# Sheet2.net
KiCad netlist of a schematic drawn in Altium Designer
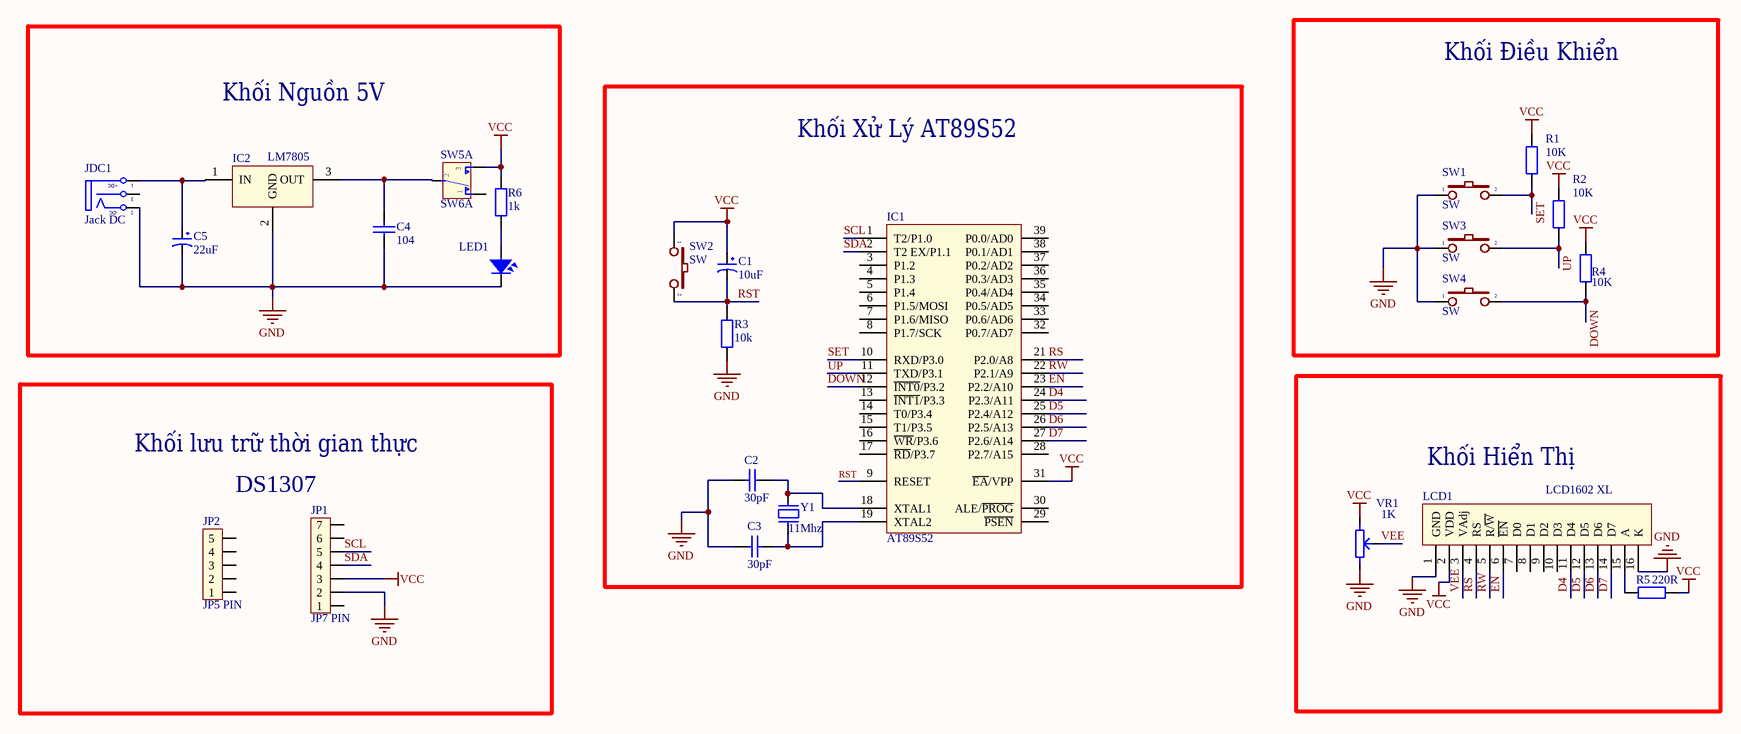
[diagram p0: Sheet2 (1).SchDoc]

(export (version "E")
  (design (tool "Eeschema 10.0.6"))
  (components
    (comp (ref "C1")
      (value "10uF")
      (footprint "tu hoa 4mm")
      (description "Cắm")
      (libsource (lib "Capacitor") (part "Tu Hoa 10uF 25V 4x7"))
    )
    (comp (ref "C2")
      (value "30pF")
      (footprint "tu gom")
      (description "Cắm")
      (libsource (lib "Capacitor") (part "Tu gom 30pF 50V"))
    )
    (comp (ref "C3")
      (value "30pF")
      (footprint "tu gom")
      (description "Cắm")
      (libsource (lib "Capacitor") (part "Tu gom 30pF 50V"))
    )
    (comp (ref "C4")
      (value "104")
      (footprint "tu gom")
      (description "Cắm")
      (libsource (lib "Capacitor") (part "Tu gom 104 50V"))
    )
    (comp (ref "C5")
      (value "22uF")
      (footprint "tu hoa 5mm")
      (description "Cắm")
      (libsource (lib "Capacitor") (part "Tu Hoa 22uF 50V 5x10"))
    )
    (comp (ref "IC1")
      (value "AT89S52")
      (footprint "DIP40/W0.6")
      (description "AT89S52, 8k Byte Flash Memory , 40 Pin")
      (libsource (lib "syhaunguyen") (part "AT89S52"))
    )
    (comp (ref "IC2")
      (value "LM7805")
      (footprint "QTO-220")
      (description "On ap +, from + 5 to + 24VDC")
      (libsource (lib "syhaunguyen") (part "LM78xx"))
    )
    (comp (ref "JDC1")
      (value "Jack DC")
      (footprint "DC-IN")
      (description "Jac DC input")
      (libsource (lib "syhaunguyen") (part "DCIN"))
    )
    (comp (ref "JP1") (value "JP7 PIN") (footprint "JP7_1") (libsource (lib "Cty1") (part "JP7")))
    (comp (ref "JP2") (value "JP5 PIN") (footprint "JP5_1") (libsource (lib "Cty1") (part "JP5")))
    (comp (ref "LCD1")
      (value "LCD1602 XL")
      (footprint "LCD1602 with Jump")
      (description "LCD 1602 Xanh Lá")
      (libsource (lib "Module") (part "LCD1602 XL"))
    )
    (comp (ref "LED1")
      (value "LED")
      (footprint "LED-5-RED")
      (description "LED Single colour Green and Red")
      (libsource (lib "syhaunguyen") (part "LED"))
    )
    (comp (ref "R1")
      (value "10K")
      (footprint "tro vach 1/4w")
      (description "Cắm")
      (libsource (lib "Resistor") (part "Tro Vach 1/4W 5% 220R"))
    )
    (comp (ref "R2")
      (value "10K")
      (footprint "tro vach 1/4w")
      (description "Cắm")
      (libsource (lib "Resistor") (part "Tro Vach 1/4W 5% 220R"))
    )
    (comp (ref "R3")
      (value "10k")
      (footprint "tro vach 1/4w")
      (description "Căm")
      (libsource (lib "Resistor") (part "Tro Vach 1/4W 5% 10k"))
    )
    (comp (ref "R4")
      (value "10K")
      (footprint "tro vach 1/4w")
      (description "Cắm")
      (libsource (lib "Resistor") (part "Tro Vach 1/4W 5% 220R"))
    )
    (comp (ref "R5")
      (value "220R")
      (footprint "tro vach 1/4w")
      (description "Cắm")
      (libsource (lib "Resistor") (part "Tro Vach 1/4W 5% 220R"))
    )
    (comp (ref "R6")
      (value "1k")
      (footprint "R1/4W")
      (description "Resistor 1/4W")
      (libsource (lib "syhaunguyen") (part "R1/4W"))
    )
    (comp (ref "SW1")
      (value "SW")
      (footprint "SW2")
      (description "Switch button 2 pin")
      (libsource (lib "syhaunguyen") (part "SW2"))
    )
    (comp (ref "SW2")
      (value "SW")
      (footprint "SW2")
      (description "Switch button 2 pin")
      (libsource (lib "syhaunguyen") (part "SW2"))
    )
    (comp (ref "SW3")
      (value "SW")
      (footprint "SW2")
      (description "Switch button 2 pin")
      (libsource (lib "syhaunguyen") (part "SW2"))
    )
    (comp (ref "SW4")
      (value "SW")
      (footprint "SW2")
      (description "Switch button 2 pin")
      (libsource (lib "syhaunguyen") (part "SW2"))
    )
    (comp (ref "SW5")
      (value "SW6A")
      (footprint "SW6")
      (description "SW-DTDP - 6 Pin")
      (libsource (lib "syhaunguyen") (part "SW6A"))
    )
    (comp (ref "VR1")
      (value "1K")
      (footprint "Bien Tro Tam Giac Dung")
      (description "Cắm")
      (libsource (lib "Resistor") (part "Bien tro tam giac 1K Dung"))
    )
    (comp (ref "Y1")
      (value "11Mhz")
      (footprint "Thach Anh 2 chan cam")
      (description "Crystal For all Crystal 2pin.")
      (libsource (lib "Component") (part "Thach Anh 2 chan Cam"))
    )
  )
  (nets
    (net (code "1") (name "/D4") (class "Default")
      (node (ref "IC1") (pin "24") (pinfunction "P2.3/A11_24") (pintype "passive"))
      (node (ref "LCD1") (pin "11") (pinfunction "D4_11") (pintype "passive"))
    )
    (net (code "2") (name "/D5") (class "Default")
      (node (ref "IC1") (pin "25") (pinfunction "P2.4/A12_25") (pintype "passive"))
      (node (ref "LCD1") (pin "12") (pinfunction "D5_12") (pintype "passive"))
    )
    (net (code "3") (name "/D6") (class "Default")
      (node (ref "IC1") (pin "26") (pinfunction "P2.5/A13_26") (pintype "passive"))
      (node (ref "LCD1") (pin "13") (pinfunction "D6_13") (pintype "passive"))
    )
    (net (code "4") (name "/D7") (class "Default")
      (node (ref "IC1") (pin "27") (pinfunction "P2.6/A14_27") (pintype "passive"))
      (node (ref "LCD1") (pin "14") (pinfunction "D7_14") (pintype "passive"))
    )
    (net (code "5") (name "/DOWN") (class "Default")
      (node (ref "IC1") (pin "12") (pinfunction "~{INT0}/P3.2_12") (pintype "passive"))
      (node (ref "R4") (pin "2") (pinfunction "2_2") (pintype "passive"))
      (node (ref "SW4") (pin "2") (pinfunction "2_2") (pintype "passive"))
    )
    (net (code "6") (name "/EN") (class "Default")
      (node (ref "IC1") (pin "23") (pinfunction "P2.2/A10_23") (pintype "passive"))
      (node (ref "LCD1") (pin "6") (pinfunction "~{EN}_6") (pintype "passive"))
    )
    (net (code "7") (name "/RS") (class "Default")
      (node (ref "IC1") (pin "21") (pinfunction "P2.0/A8_21") (pintype "passive"))
      (node (ref "LCD1") (pin "4") (pinfunction "RS_4") (pintype "passive"))
    )
    (net (code "8") (name "/RST") (class "Default")
      (node (ref "C1") (pin "2") (pinfunction "2_2") (pintype "passive"))
      (node (ref "IC1") (pin "9") (pinfunction "RESET_9") (pintype "passive"))
      (node (ref "R3") (pin "2") (pinfunction "2_2") (pintype "passive"))
      (node (ref "SW2") (pin "2") (pinfunction "2_2") (pintype "passive"))
    )
    (net (code "9") (name "/RW") (class "Default")
      (node (ref "IC1") (pin "22") (pinfunction "P2.1/A9_22") (pintype "passive"))
      (node (ref "LCD1") (pin "5") (pinfunction "R/~{W}_5") (pintype "passive"))
    )
    (net (code "10") (name "/SCL") (class "Default")
      (node (ref "IC1") (pin "1") (pinfunction "T2/P1.0_1") (pintype "passive"))
      (node (ref "JP1") (pin "5") (pinfunction "5_5") (pintype "passive"))
    )
    (net (code "11") (name "/SDA") (class "Default")
      (node (ref "IC1") (pin "2") (pinfunction "T2_EX/P1.1_2") (pintype "passive"))
      (node (ref "JP1") (pin "4") (pinfunction "4_4") (pintype "passive"))
    )
    (net (code "12") (name "/SET") (class "Default")
      (node (ref "IC1") (pin "10") (pinfunction "RXD/P3.0_10") (pintype "passive"))
      (node (ref "R1") (pin "2") (pinfunction "2_2") (pintype "passive"))
      (node (ref "SW1") (pin "2") (pinfunction "2_2") (pintype "passive"))
    )
    (net (code "13") (name "/UP") (class "Default")
      (node (ref "IC1") (pin "11") (pinfunction "TXD/P3.1_11") (pintype "passive"))
      (node (ref "R2") (pin "2") (pinfunction "2_2") (pintype "passive"))
      (node (ref "SW3") (pin "2") (pinfunction "2_2") (pintype "passive"))
    )
    (net (code "14") (name "/VEE") (class "Default")
      (node (ref "LCD1") (pin "3") (pinfunction "VAdj_3") (pintype "passive"))
      (node (ref "VR1") (pin "2") (pinfunction "2_2") (pintype "passive"))
    )
    (net (code "15") (name "GND") (class "Default")
      (node (ref "C2") (pin "2") (pinfunction "2_2") (pintype "passive"))
      (node (ref "C3") (pin "2") (pinfunction "2_2") (pintype "passive"))
      (node (ref "C4") (pin "2") (pinfunction "2_2") (pintype "passive"))
      (node (ref "C5") (pin "2") (pinfunction "2_2") (pintype "passive"))
      (node (ref "IC1") (pin "20") (pinfunction "GND_20") (pintype "power_in"))
      (node (ref "IC2") (pin "2") (pinfunction "GND_2") (pintype "passive"))
      (node (ref "JDC1") (pin "2") (pinfunction "TN_2") (pintype "passive"))
      (node (ref "JP1") (pin "2") (pinfunction "2_2") (pintype "passive"))
      (node (ref "LCD1") (pin "1") (pinfunction "GND_1") (pintype "passive"))
      (node (ref "LCD1") (pin "16") (pinfunction "K_16") (pintype "passive"))
      (node (ref "LED1") (pin "2") (pinfunction "2_2") (pintype "passive"))
      (node (ref "R3") (pin "1") (pinfunction "1_1") (pintype "passive"))
      (node (ref "SW1") (pin "1") (pinfunction "1_1") (pintype "passive"))
      (node (ref "SW3") (pin "1") (pinfunction "1_1") (pintype "passive"))
      (node (ref "SW4") (pin "1") (pinfunction "1_1") (pintype "passive"))
      (node (ref "VR1") (pin "3") (pinfunction "3_3") (pintype "passive"))
    )
    (net (code "16") (name "Net-(IC1-XTAL1)") (class "Default")
      (node (ref "C2") (pin "1") (pinfunction "1_1") (pintype "passive"))
      (node (ref "IC1") (pin "18") (pinfunction "XTAL1_18") (pintype "passive"))
      (node (ref "Y1") (pin "2") (pinfunction "2_2") (pintype "passive"))
    )
    (net (code "17") (name "Net-(IC1-XTAL2)") (class "Default")
      (node (ref "C3") (pin "1") (pinfunction "1_1") (pintype "passive"))
      (node (ref "IC1") (pin "19") (pinfunction "XTAL2_19") (pintype "passive"))
      (node (ref "Y1") (pin "1") (pinfunction "1_1") (pintype "passive"))
    )
    (net (code "18") (name "Net-(IC2-IN)") (class "Default")
      (node (ref "C5") (pin "1") (pinfunction "1_1") (pintype "passive"))
      (node (ref "IC2") (pin "1") (pinfunction "IN_1") (pintype "passive"))
      (node (ref "JDC1") (pin "1") (pinfunction "T_1") (pintype "passive"))
    )
    (net (code "19") (name "Net-(IC2-OUT)") (class "Default")
      (node (ref "C4") (pin "1") (pinfunction "1_1") (pintype "passive"))
      (node (ref "IC2") (pin "3") (pinfunction "OUT_3") (pintype "passive"))
      (node (ref "SW5") (pin "2") (pinfunction "2_2") (pintype "passive"))
    )
    (net (code "20") (name "Net-(LCD1-A)") (class "Default")
      (node (ref "LCD1") (pin "15") (pinfunction "A_15") (pintype "passive"))
      (node (ref "R5") (pin "2") (pinfunction "2_2") (pintype "passive"))
    )
    (net (code "21") (name "Net-(LED1-Pad1)") (class "Default")
      (node (ref "LED1") (pin "1") (pinfunction "1_1") (pintype "passive"))
      (node (ref "R6") (pin "1") (pinfunction "1_1") (pintype "passive"))
    )
    (net (code "22") (name "VCC") (class "Default")
      (node (ref "C1") (pin "1") (pinfunction "1_1") (pintype "passive"))
      (node (ref "IC1") (pin "31") (pinfunction "~{EA}/VPP_31") (pintype "passive"))
      (node (ref "IC1") (pin "40") (pinfunction "VCC_40") (pintype "power_in"))
      (node (ref "JP1") (pin "3") (pinfunction "3_3") (pintype "passive"))
      (node (ref "LCD1") (pin "2") (pinfunction "VDD_2") (pintype "passive"))
      (node (ref "R1") (pin "1") (pinfunction "1_1") (pintype "passive"))
      (node (ref "R2") (pin "1") (pinfunction "1_1") (pintype "passive"))
      (node (ref "R4") (pin "1") (pinfunction "1_1") (pintype "passive"))
      (node (ref "R5") (pin "1") (pinfunction "1_1") (pintype "passive"))
      (node (ref "R6") (pin "2") (pinfunction "2_2") (pintype "passive"))
      (node (ref "SW2") (pin "1") (pinfunction "1_1") (pintype "passive"))
      (node (ref "SW5") (pin "3") (pinfunction "3_3") (pintype "passive"))
      (node (ref "VR1") (pin "1") (pinfunction "1_1") (pintype "passive"))
    )
    (net (code "23") (name "unconnected-(IC1-ALE{slash}~{PROG}-Pad30)") (class "Default")
      (node (ref "IC1") (pin "30") (pinfunction "ALE/~{PROG}_30") (pintype "passive"))
    )
    (net (code "24") (name "unconnected-(IC1-P0.0{slash}AD0-Pad39)") (class "Default")
      (node (ref "IC1") (pin "39") (pinfunction "P0.0/AD0_39") (pintype "passive"))
    )
    (net (code "25") (name "unconnected-(IC1-P0.1{slash}AD1-Pad38)") (class "Default")
      (node (ref "IC1") (pin "38") (pinfunction "P0.1/AD1_38") (pintype "passive"))
    )
    (net (code "26") (name "unconnected-(IC1-P0.2{slash}AD2-Pad37)") (class "Default")
      (node (ref "IC1") (pin "37") (pinfunction "P0.2/AD2_37") (pintype "passive"))
    )
    (net (code "27") (name "unconnected-(IC1-P0.3{slash}AD3-Pad36)") (class "Default")
      (node (ref "IC1") (pin "36") (pinfunction "P0.3/AD3_36") (pintype "passive"))
    )
    (net (code "28") (name "unconnected-(IC1-P0.4{slash}AD4-Pad35)") (class "Default")
      (node (ref "IC1") (pin "35") (pinfunction "P0.4/AD4_35") (pintype "passive"))
    )
    (net (code "29") (name "unconnected-(IC1-P0.5{slash}AD5-Pad34)") (class "Default")
      (node (ref "IC1") (pin "34") (pinfunction "P0.5/AD5_34") (pintype "passive"))
    )
    (net (code "30") (name "unconnected-(IC1-P0.6{slash}AD6-Pad33)") (class "Default")
      (node (ref "IC1") (pin "33") (pinfunction "P0.6/AD6_33") (pintype "passive"))
    )
    (net (code "31") (name "unconnected-(IC1-P0.7{slash}AD7-Pad32)") (class "Default")
      (node (ref "IC1") (pin "32") (pinfunction "P0.7/AD7_32") (pintype "passive"))
    )
    (net (code "32") (name "unconnected-(IC1-P1.2-Pad3)") (class "Default")
      (node (ref "IC1") (pin "3") (pinfunction "P1.2_3") (pintype "passive"))
    )
    (net (code "33") (name "unconnected-(IC1-P1.3-Pad4)") (class "Default")
      (node (ref "IC1") (pin "4") (pinfunction "P1.3_4") (pintype "passive"))
    )
    (net (code "34") (name "unconnected-(IC1-P1.4-Pad5)") (class "Default")
      (node (ref "IC1") (pin "5") (pinfunction "P1.4_5") (pintype "passive"))
    )
    (net (code "35") (name "unconnected-(IC1-P1.5{slash}MOSI-Pad6)") (class "Default")
      (node (ref "IC1") (pin "6") (pinfunction "P1.5/MOSI_6") (pintype "passive"))
    )
    (net (code "36") (name "unconnected-(IC1-P1.6{slash}MISO-Pad7)") (class "Default")
      (node (ref "IC1") (pin "7") (pinfunction "P1.6/MISO_7") (pintype "passive"))
    )
    (net (code "37") (name "unconnected-(IC1-P1.7{slash}SCK-Pad8)") (class "Default")
      (node (ref "IC1") (pin "8") (pinfunction "P1.7/SCK_8") (pintype "passive"))
    )
    (net (code "38") (name "unconnected-(IC1-P2.7{slash}A15-Pad28)") (class "Default")
      (node (ref "IC1") (pin "28") (pinfunction "P2.7/A15_28") (pintype "passive"))
    )
    (net (code "39") (name "unconnected-(IC1-T0{slash}P3.4-Pad14)") (class "Default")
      (node (ref "IC1") (pin "14") (pinfunction "T0/P3.4_14") (pintype "passive"))
    )
    (net (code "40") (name "unconnected-(IC1-T1{slash}P3.5-Pad15)") (class "Default")
      (node (ref "IC1") (pin "15") (pinfunction "T1/P3.5_15") (pintype "passive"))
    )
    (net (code "41") (name "unconnected-(IC1-~{INT1}{slash}P3.3-Pad13)") (class "Default")
      (node (ref "IC1") (pin "13") (pinfunction "~{INT1}/P3.3_13") (pintype "passive"))
    )
    (net (code "42") (name "unconnected-(IC1-~{PSEN}-Pad29)") (class "Default")
      (node (ref "IC1") (pin "29") (pinfunction "~{PSEN}_29") (pintype "passive"))
    )
    (net (code "43") (name "unconnected-(IC1-~{RD}{slash}P3.7-Pad17)") (class "Default")
      (node (ref "IC1") (pin "17") (pinfunction "~{RD}/P3.7_17") (pintype "passive"))
    )
    (net (code "44") (name "unconnected-(IC1-~{WR}{slash}P3.6-Pad16)") (class "Default")
      (node (ref "IC1") (pin "16") (pinfunction "~{WR}/P3.6_16") (pintype "passive"))
    )
    (net (code "45") (name "unconnected-(JDC1-S-Pad3)") (class "Default")
      (node (ref "JDC1") (pin "3") (pinfunction "S_3") (pintype "power_in"))
    )
    (net (code "46") (name "unconnected-(JP1-Pad1)") (class "Default")
      (node (ref "JP1") (pin "1") (pinfunction "1_1") (pintype "passive"))
    )
    (net (code "47") (name "unconnected-(JP1-Pad6)") (class "Default")
      (node (ref "JP1") (pin "6") (pinfunction "6_6") (pintype "passive"))
    )
    (net (code "48") (name "unconnected-(JP1-Pad7)") (class "Default")
      (node (ref "JP1") (pin "7") (pinfunction "7_7") (pintype "passive"))
    )
    (net (code "49") (name "unconnected-(JP2-Pad1)") (class "Default")
      (node (ref "JP2") (pin "1") (pinfunction "1_1") (pintype "passive"))
    )
    (net (code "50") (name "unconnected-(JP2-Pad2)") (class "Default")
      (node (ref "JP2") (pin "2") (pinfunction "2_2") (pintype "passive"))
    )
    (net (code "51") (name "unconnected-(JP2-Pad3)") (class "Default")
      (node (ref "JP2") (pin "3") (pinfunction "3_3") (pintype "passive"))
    )
    (net (code "52") (name "unconnected-(JP2-Pad4)") (class "Default")
      (node (ref "JP2") (pin "4") (pinfunction "4_4") (pintype "passive"))
    )
    (net (code "53") (name "unconnected-(JP2-Pad5)") (class "Default")
      (node (ref "JP2") (pin "5") (pinfunction "5_5") (pintype "passive"))
    )
    (net (code "54") (name "unconnected-(LCD1-D0-Pad7)") (class "Default")
      (node (ref "LCD1") (pin "7") (pinfunction "D0_7") (pintype "passive"))
    )
    (net (code "55") (name "unconnected-(LCD1-D1-Pad8)") (class "Default")
      (node (ref "LCD1") (pin "8") (pinfunction "D1_8") (pintype "passive"))
    )
    (net (code "56") (name "unconnected-(LCD1-D2-Pad9)") (class "Default")
      (node (ref "LCD1") (pin "9") (pinfunction "D2_9") (pintype "passive"))
    )
    (net (code "57") (name "unconnected-(LCD1-D3-Pad10)") (class "Default")
      (node (ref "LCD1") (pin "10") (pinfunction "D3_10") (pintype "passive"))
    )
    (net (code "58") (name "unconnected-(SW5-Pad1)") (class "Default")
      (node (ref "SW5") (pin "1") (pinfunction "1_1") (pintype "passive"))
    )
  )
)
